# ZP_Force_Plates.net
KiCad netlist of a schematic drawn in Altium Designer
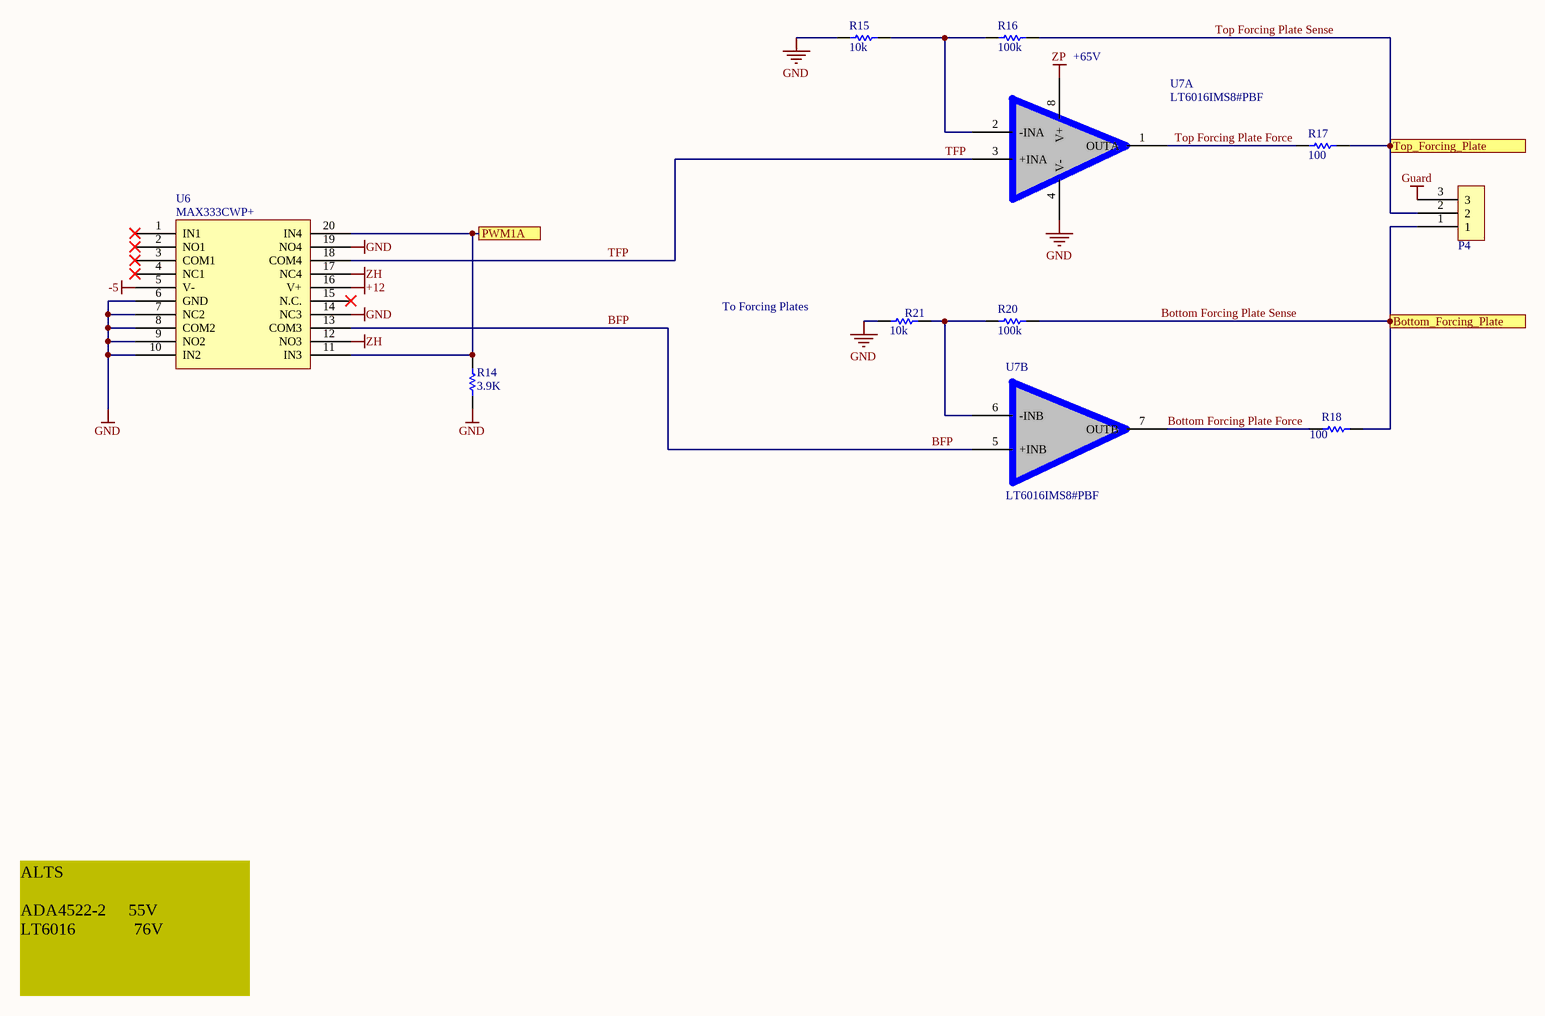
[diagram p0: ZP_Force_Plates.SchDoc]

(export (version "E")
  (design (tool "Eeschema 10.0.6"))
  (components
    (comp (ref "P4")
      (value "Triax_Conn")
      (footprint "Triax_Conn")
      (libsource (lib "ZLS_Schematic_lib") (part "Triax_Conn"))
    )
    (comp (ref "R14")
      (value "3.9K")
      (footprint "RESC0402(1005)_M")
      (libsource (lib "Altium Content Vault") (part "CMP-1011-00463-1"))
    )
    (comp (ref "R15")
      (value "10k")
      (footprint "RESC0402(1005)_M")
      (libsource (lib "Altium Content Vault") (part "CMP-1011-00463-1"))
    )
    (comp (ref "R16")
      (value "100k")
      (footprint "RESC0402(1005)_M")
      (libsource (lib "Altium Content Vault") (part "CMP-1011-00463-1"))
    )
    (comp (ref "R17")
      (value "100")
      (footprint "RESC0402(1005)_M")
      (libsource (lib "Altium Content Vault") (part "CMP-1011-00463-1"))
    )
    (comp (ref "R18")
      (value "100")
      (footprint "RESC0402(1005)_M")
      (libsource (lib "Altium Content Vault") (part "CMP-1011-00463-1"))
    )
    (comp (ref "R20")
      (value "100k")
      (footprint "RESC0402(1005)_M")
      (libsource (lib "Altium Content Vault") (part "CMP-1011-00463-1"))
    )
    (comp (ref "R21")
      (value "10k")
      (footprint "RESC0402(1005)_M")
      (libsource (lib "Altium Content Vault") (part "CMP-1011-00463-1"))
    )
    (comp (ref "U6")
      (value "MAX333CWP+")
      (footprint "TSOP65P640X90-20N")
      (description "IC SWITCH QUAD SPDT 20TSSOP")
      (fields (field (name "MANUFACTURER") "Maxim") (field (name "MANUFACTURER PART NUMBER") "MAX333AEUP+"))
      (libsource (lib "ZLS_Schematic_lib") (part "MAX333CWP+"))
    )
    (comp (ref "U7")
      (value "LT6016")
      (footprint "LT6016")
      (description "IC OPAMP GP 3.3MHZ RRO 8MSOP")
      (fields (field (name "SUPPLIER PART NUMBER 1") "LT6016IMS8#PBF"))
      (libsource (lib "ZLS_Schematic_lib") (part "LT6016"))
    )
  )
  (nets
    (net (code "1") (name "+12") (class "Default")
      (node (ref "U6") (pin "16") (pinfunction "V+_16") (pintype "power_in"))
    )
    (net (code "2") (name "-5") (class "Default")
      (node (ref "U6") (pin "5") (pinfunction "V-_5") (pintype "power_in"))
    )
    (net (code "3") (name "/BFP") (class "Default")
      (node (ref "U6") (pin "13") (pinfunction "COM3_13") (pintype "passive"))
      (node (ref "U7") (pin "5") (pinfunction "+INB_5") (pintype "passive"))
    )
    (net (code "4") (name "/Bottom Forcing Plate Force") (class "Default")
      (node (ref "R18") (pin "1") (pinfunction "1_1") (pintype "passive"))
      (node (ref "U7") (pin "7") (pinfunction "OUTB_7") (pintype "passive"))
    )
    (net (code "5") (name "/Bottom Forcing Plate Sense") (class "Default")
      (node (ref "P4") (pin "1") (pinfunction "1_1") (pintype "passive"))
      (node (ref "R18") (pin "2") (pinfunction "2_2") (pintype "passive"))
      (node (ref "R20") (pin "2") (pinfunction "2_2") (pintype "passive"))
    )
    (net (code "6") (name "/PWM1A") (class "Default")
      (node (ref "R14") (pin "2") (pinfunction "2_2") (pintype "passive"))
      (node (ref "U6") (pin "11") (pinfunction "IN3_11") (pintype "passive"))
      (node (ref "U6") (pin "20") (pinfunction "IN4_20") (pintype "passive"))
    )
    (net (code "7") (name "/TFP") (class "Default")
      (node (ref "U6") (pin "18") (pinfunction "COM4_18") (pintype "passive"))
      (node (ref "U7") (pin "3") (pinfunction "+INA_3") (pintype "passive"))
    )
    (net (code "8") (name "/Top Forcing Plate Force") (class "Default")
      (node (ref "R17") (pin "1") (pinfunction "1_1") (pintype "passive"))
      (node (ref "U7") (pin "1") (pinfunction "OUTA_1") (pintype "passive"))
    )
    (net (code "9") (name "/Top Forcing Plate Sense") (class "Default")
      (node (ref "P4") (pin "2") (pinfunction "2_2") (pintype "passive"))
      (node (ref "R16") (pin "2") (pinfunction "2_2") (pintype "passive"))
      (node (ref "R17") (pin "2") (pinfunction "2_2") (pintype "passive"))
    )
    (net (code "10") (name "GND") (class "Default")
      (node (ref "R14") (pin "1") (pinfunction "1_1") (pintype "passive"))
      (node (ref "R15") (pin "1") (pinfunction "1_1") (pintype "passive"))
      (node (ref "R21") (pin "1") (pinfunction "1_1") (pintype "passive"))
      (node (ref "U6") (pin "10") (pinfunction "IN2_10") (pintype "passive"))
      (node (ref "U6") (pin "14") (pinfunction "NC3_14") (pintype "passive"))
      (node (ref "U6") (pin "19") (pinfunction "NO4_19") (pintype "passive"))
      (node (ref "U6") (pin "6") (pinfunction "GND_6") (pintype "passive"))
      (node (ref "U6") (pin "7") (pinfunction "NC2_7") (pintype "passive"))
      (node (ref "U6") (pin "8") (pinfunction "COM2_8") (pintype "passive"))
      (node (ref "U6") (pin "9") (pinfunction "NO2_9") (pintype "passive"))
      (node (ref "U7") (pin "4") (pinfunction "V-_4") (pintype "passive"))
    )
    (net (code "11") (name "Guard") (class "Default")
      (node (ref "P4") (pin "3") (pinfunction "3_3") (pintype "passive"))
    )
    (net (code "12") (name "Net-(U7A--INA)") (class "Default")
      (node (ref "R15") (pin "2") (pinfunction "2_2") (pintype "passive"))
      (node (ref "R16") (pin "1") (pinfunction "1_1") (pintype "passive"))
      (node (ref "U7") (pin "2") (pinfunction "-INA_2") (pintype "passive"))
    )
    (net (code "13") (name "Net-(U7B--INB)") (class "Default")
      (node (ref "R20") (pin "1") (pinfunction "1_1") (pintype "passive"))
      (node (ref "R21") (pin "2") (pinfunction "2_2") (pintype "passive"))
      (node (ref "U7") (pin "6") (pinfunction "-INB_6") (pintype "passive"))
    )
    (net (code "14") (name "ZH") (class "Default")
      (node (ref "U6") (pin "12") (pinfunction "NO3_12") (pintype "passive"))
      (node (ref "U6") (pin "17") (pinfunction "NC4_17") (pintype "passive"))
    )
    (net (code "15") (name "ZP") (class "Default")
      (node (ref "U7") (pin "8") (pinfunction "V+_8") (pintype "passive"))
    )
    (net (code "16") (name "unconnected-(U6-COM1-Pad3)") (class "Default")
      (node (ref "U6") (pin "3") (pinfunction "COM1_3") (pintype "passive+no_connect"))
    )
    (net (code "17") (name "unconnected-(U6-IN1-Pad1)") (class "Default")
      (node (ref "U6") (pin "1") (pinfunction "IN1_1") (pintype "passive+no_connect"))
    )
    (net (code "18") (name "unconnected-(U6-N.C.-Pad15)") (class "Default")
      (node (ref "U6") (pin "15") (pinfunction "N.C._15") (pintype "passive+no_connect"))
    )
    (net (code "19") (name "unconnected-(U6-NC1-Pad4)") (class "Default")
      (node (ref "U6") (pin "4") (pinfunction "NC1_4") (pintype "passive+no_connect"))
    )
    (net (code "20") (name "unconnected-(U6-NO1-Pad2)") (class "Default")
      (node (ref "U6") (pin "2") (pinfunction "NO1_2") (pintype "passive+no_connect"))
    )
  )
)
